# TXB0104_breakout_voltage_breakout.net
KiCad netlist of a schematic drawn in EAGLE
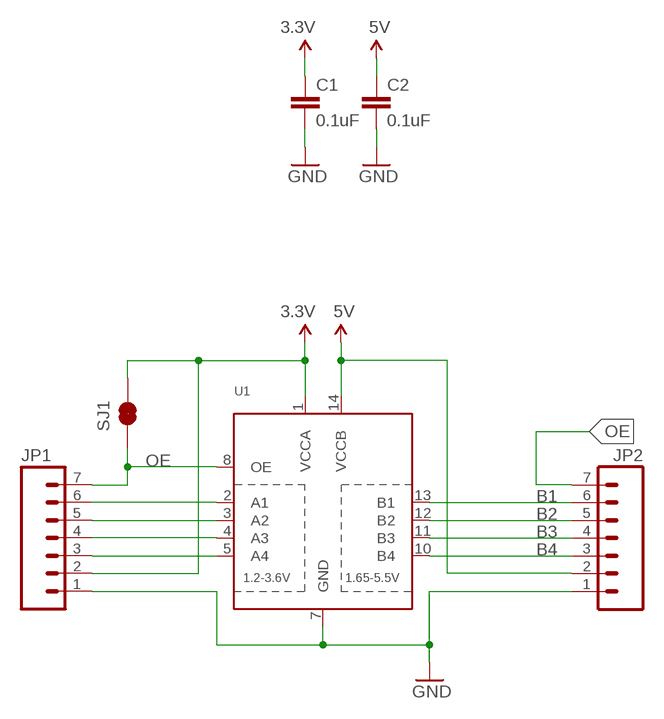
[diagram p0: schematic, sheet 1]

(export (version "E")
  (design (tool "Eeschema 10.0.6"))
  (components
    (comp (ref "C1")
      (value "0.1uF")
      (footprint "eagle-import:0603-CAP")
      (libsource (lib "eagle-import") (part "0.1UF-25V(+80/-20%)(0603)"))
    )
    (comp (ref "C2")
      (value "0.1uF")
      (footprint "eagle-import:0603-CAP")
      (libsource (lib "eagle-import") (part "0.1UF-25V(+80/-20%)(0603)"))
    )
    (comp (ref "JP1")
      (value "M07")
      (footprint "eagle-import:1X07")
      (libsource (lib "eagle-import") (part "M07"))
    )
    (comp (ref "JP2")
      (value "M07")
      (footprint "eagle-import:1X07")
      (libsource (lib "eagle-import") (part "M07"))
    )
    (comp (ref "SJ1")
      (value "SOLDERJUMPERNC2")
      (footprint "eagle-import:SJ_2S-NOTRACE")
      (libsource (lib "eagle-import") (part "SOLDERJUMPERNC2"))
    )
    (comp (ref "U1")
      (value "TXB0104PWRSOIC14")
      (footprint "eagle-import:SO14")
      (libsource (lib "eagle-import") (part "TXB0104PWRSOIC14"))
    )
  )
  (nets
    (net (code "1") (name "/B1") (class "Default")
      (node (ref "JP2") (pin "6") (pinfunction "6_6") (pintype "passive"))
      (node (ref "U1") (pin "13") (pinfunction "B1_13") (pintype "bidirectional"))
    )
    (net (code "2") (name "/B2") (class "Default")
      (node (ref "JP2") (pin "5") (pinfunction "5_5") (pintype "passive"))
      (node (ref "U1") (pin "12") (pinfunction "B2_12") (pintype "bidirectional"))
    )
    (net (code "3") (name "/B3") (class "Default")
      (node (ref "JP2") (pin "4") (pinfunction "4_4") (pintype "passive"))
      (node (ref "U1") (pin "11") (pinfunction "B3_11") (pintype "bidirectional"))
    )
    (net (code "4") (name "/B4") (class "Default")
      (node (ref "JP2") (pin "3") (pinfunction "3_3") (pintype "passive"))
      (node (ref "U1") (pin "10") (pinfunction "B4_10") (pintype "bidirectional"))
    )
    (net (code "5") (name "3.3V") (class "Default")
      (node (ref "C1") (pin "1") (pinfunction "1_1") (pintype "passive"))
      (node (ref "JP1") (pin "2") (pinfunction "2_2") (pintype "passive"))
      (node (ref "SJ1") (pin "2") (pinfunction "2_2") (pintype "passive"))
      (node (ref "U1") (pin "1") (pinfunction "VCCA_1") (pintype "bidirectional"))
    )
    (net (code "6") (name "5V") (class "Default")
      (node (ref "C2") (pin "1") (pinfunction "1_1") (pintype "passive"))
      (node (ref "JP2") (pin "2") (pinfunction "2_2") (pintype "passive"))
      (node (ref "U1") (pin "14") (pinfunction "VCCB_14") (pintype "bidirectional"))
    )
    (net (code "7") (name "GND") (class "Default")
      (node (ref "C1") (pin "2") (pinfunction "2_2") (pintype "passive"))
      (node (ref "C2") (pin "2") (pinfunction "2_2") (pintype "passive"))
      (node (ref "JP1") (pin "1") (pinfunction "1_1") (pintype "passive"))
      (node (ref "JP2") (pin "1") (pinfunction "1_1") (pintype "passive"))
      (node (ref "U1") (pin "7") (pinfunction "GND_7") (pintype "bidirectional"))
    )
    (net (code "8") (name "Net-(U1-A1)") (class "Default")
      (node (ref "JP1") (pin "6") (pinfunction "6_6") (pintype "passive"))
      (node (ref "U1") (pin "2") (pinfunction "A1_2") (pintype "bidirectional"))
    )
    (net (code "9") (name "Net-(U1-A2)") (class "Default")
      (node (ref "JP1") (pin "5") (pinfunction "5_5") (pintype "passive"))
      (node (ref "U1") (pin "3") (pinfunction "A2_3") (pintype "bidirectional"))
    )
    (net (code "10") (name "Net-(U1-A3)") (class "Default")
      (node (ref "JP1") (pin "4") (pinfunction "4_4") (pintype "passive"))
      (node (ref "U1") (pin "4") (pinfunction "A3_4") (pintype "bidirectional"))
    )
    (net (code "11") (name "Net-(U1-A4)") (class "Default")
      (node (ref "JP1") (pin "3") (pinfunction "3_3") (pintype "passive"))
      (node (ref "U1") (pin "5") (pinfunction "A4_5") (pintype "bidirectional"))
    )
    (net (code "12") (name "OE") (class "Default")
      (node (ref "JP1") (pin "7") (pinfunction "7_7") (pintype "passive"))
      (node (ref "JP2") (pin "7") (pinfunction "7_7") (pintype "passive"))
      (node (ref "SJ1") (pin "1") (pinfunction "1_1") (pintype "passive"))
      (node (ref "U1") (pin "8") (pinfunction "OE_8") (pintype "bidirectional"))
    )
  )
)
